# driver_board_one_module.net
KiCad netlist of a schematic drawn in EAGLE
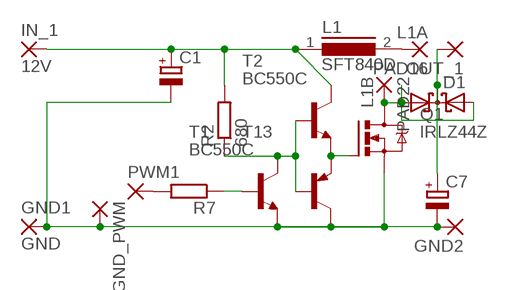
[diagram p0: schematic, sheet 1]

(export (version "E")
  (design (tool "Eeschema 10.0.6"))
  (components
    (comp (ref "C1")
      (value "CPOL-EUE5-8.5")
      (footprint "eagle-import:E5-8,5")
      (libsource (lib "eagle-import") (part "CPOL-EUE5-8.5"))
    )
    (comp (ref "C7")
      (value "CPOL-EUE5-8.5")
      (footprint "eagle-import:E5-8,5")
      (libsource (lib "eagle-import") (part "CPOL-EUE5-8.5"))
    )
    (comp (ref "D1")
      (value "DIODE_2SCHOTTKY-SOT93V")
      (footprint "eagle-import:SOT93S")
      (libsource (lib "eagle-import") (part "DIODE_2SCHOTTKY-SOT93V"))
    )
    (comp (ref "GND1")
      (value "GND")
      (footprint "eagle-import:3,81_1,3")
      (libsource (lib "eagle-import") (part "3,81/1,3"))
    )
    (comp (ref "GND2")
      (value "3,81/1,3")
      (footprint "eagle-import:3,81_1,3")
      (libsource (lib "eagle-import") (part "3,81/1,3"))
    )
    (comp (ref "GND_PWM")
      (value "2,54/0,8")
      (footprint "eagle-import:2,54_0,8")
      (libsource (lib "eagle-import") (part "2,54/0,8"))
    )
    (comp (ref "IN_1")
      (value "12V")
      (footprint "eagle-import:3,81_1,3")
      (libsource (lib "eagle-import") (part "3,81/1,3"))
    )
    (comp (ref "L1")
      (value "SFT840D")
      (footprint "eagle-import:SFT840D")
      (libsource (lib "eagle-import") (part "SFT840D"))
    )
    (comp (ref "OUT_1")
      (value "3,81/1,3")
      (footprint "eagle-import:3,81_1,3")
      (libsource (lib "eagle-import") (part "3,81/1,3"))
    )
    (comp (ref "PAD16")
      (value "L1A")
      (footprint "eagle-import:3,81_1,1")
      (libsource (lib "eagle-import") (part "3,81/1,1"))
    )
    (comp (ref "PAD22")
      (value "L1B")
      (footprint "eagle-import:3,81_1,1")
      (libsource (lib "eagle-import") (part "3,81/1,1"))
    )
    (comp (ref "PWM1")
      (value "2,54/0,8")
      (footprint "eagle-import:2,54_0,8")
      (libsource (lib "eagle-import") (part "2,54/0,8"))
    )
    (comp (ref "Q1")
      (value "IRLZ44Z")
      (footprint "eagle-import:TO220BH")
      (libsource (lib "eagle-import") (part "IRLZ44Z"))
    )
    (comp (ref "R2")
      (value "680")
      (footprint "eagle-import:0204_7")
      (libsource (lib "eagle-import") (part "R-EU_0204/7"))
    )
    (comp (ref "R7")
      (value "R-EU_0207/7")
      (footprint "eagle-import:0207_7")
      (libsource (lib "eagle-import") (part "R-EU_0207/7"))
    )
    (comp (ref "T1")
      (value "BC550C")
      (footprint "eagle-import:TO92-EBC")
      (libsource (lib "eagle-import") (part "BC550C"))
    )
    (comp (ref "T2")
      (value "BC550C")
      (footprint "eagle-import:TO92-EBC")
      (libsource (lib "eagle-import") (part "BC550C"))
    )
    (comp (ref "T13")
      (value "BC557C-PNP-TO92-EBC")
      (footprint "eagle-import:TO92-EBC")
      (libsource (lib "eagle-import") (part "-PNP-TO92-EBCBC557C"))
    )
  )
  (nets
    (net (code "1") (name "Net-(GND1-P)") (class "Default")
      (node (ref "C1") (pin "-") (pinfunction "-_-") (pintype "passive"))
      (node (ref "C7") (pin "-") (pinfunction "-_-") (pintype "passive"))
      (node (ref "GND1") (pin "1") (pinfunction "P_1") (pintype "passive"))
      (node (ref "GND2") (pin "1") (pinfunction "P_1") (pintype "passive"))
      (node (ref "GND_PWM") (pin "1") (pinfunction "P_1") (pintype "passive"))
      (node (ref "Q1") (pin "S") (pinfunction "S_S") (pintype "passive"))
      (node (ref "T1") (pin "E") (pinfunction "E_E") (pintype "passive"))
      (node (ref "T13") (pin "C") (pinfunction "C_C") (pintype "passive"))
    )
    (net (code "2") (name "Net-(IN_1-P)") (class "Default")
      (node (ref "C1") (pin "+") (pinfunction "+_+") (pintype "passive"))
      (node (ref "IN_1") (pin "1") (pinfunction "P_1") (pintype "passive"))
      (node (ref "L1") (pin "1") (pinfunction "1_1") (pintype "passive"))
      (node (ref "R2") (pin "2") (pinfunction "2_2") (pintype "passive"))
      (node (ref "T2") (pin "C") (pinfunction "C_C") (pintype "passive"))
    )
    (net (code "3") (name "Net-(OUT_1-P)") (class "Default")
      (node (ref "C7") (pin "+") (pinfunction "+_+") (pintype "passive"))
      (node (ref "D1") (pin "C") (pinfunction "C_C") (pintype "passive"))
      (node (ref "OUT_1") (pin "1") (pinfunction "P_1") (pintype "passive"))
    )
    (net (code "4") (name "Net-(PAD16-P)") (class "Default")
      (node (ref "L1") (pin "2") (pinfunction "2_2") (pintype "passive"))
      (node (ref "PAD16") (pin "1") (pinfunction "P_1") (pintype "passive"))
    )
    (net (code "5") (name "Net-(PAD22-P)") (class "Default")
      (node (ref "D1") (pin "A1") (pinfunction "A1_A1") (pintype "passive"))
      (node (ref "D1") (pin "A2") (pinfunction "A2_A2") (pintype "passive"))
      (node (ref "PAD22") (pin "1") (pinfunction "P_1") (pintype "passive"))
      (node (ref "Q1") (pin "D") (pinfunction "D_D") (pintype "passive"))
    )
    (net (code "6") (name "Net-(PWM1-P)") (class "Default")
      (node (ref "PWM1") (pin "1") (pinfunction "P_1") (pintype "passive"))
      (node (ref "R7") (pin "2") (pinfunction "2_2") (pintype "passive"))
    )
    (net (code "7") (name "Net-(Q1-PadG)") (class "Default")
      (node (ref "Q1") (pin "G") (pinfunction "G_G") (pintype "passive"))
      (node (ref "T13") (pin "E") (pinfunction "E_E") (pintype "passive"))
      (node (ref "T2") (pin "E") (pinfunction "E_E") (pintype "passive"))
    )
    (net (code "8") (name "Net-(R2-Pad1)") (class "Default")
      (node (ref "R2") (pin "1") (pinfunction "1_1") (pintype "passive"))
      (node (ref "T1") (pin "C") (pinfunction "C_C") (pintype "passive"))
      (node (ref "T13") (pin "B") (pinfunction "B_B") (pintype "passive"))
      (node (ref "T2") (pin "B") (pinfunction "B_B") (pintype "passive"))
    )
    (net (code "9") (name "Net-(R7-Pad1)") (class "Default")
      (node (ref "R7") (pin "1") (pinfunction "1_1") (pintype "passive"))
      (node (ref "T1") (pin "B") (pinfunction "B_B") (pintype "passive"))
    )
  )
)
